# MCU.net
KiCad netlist of a schematic drawn in Altium Designer
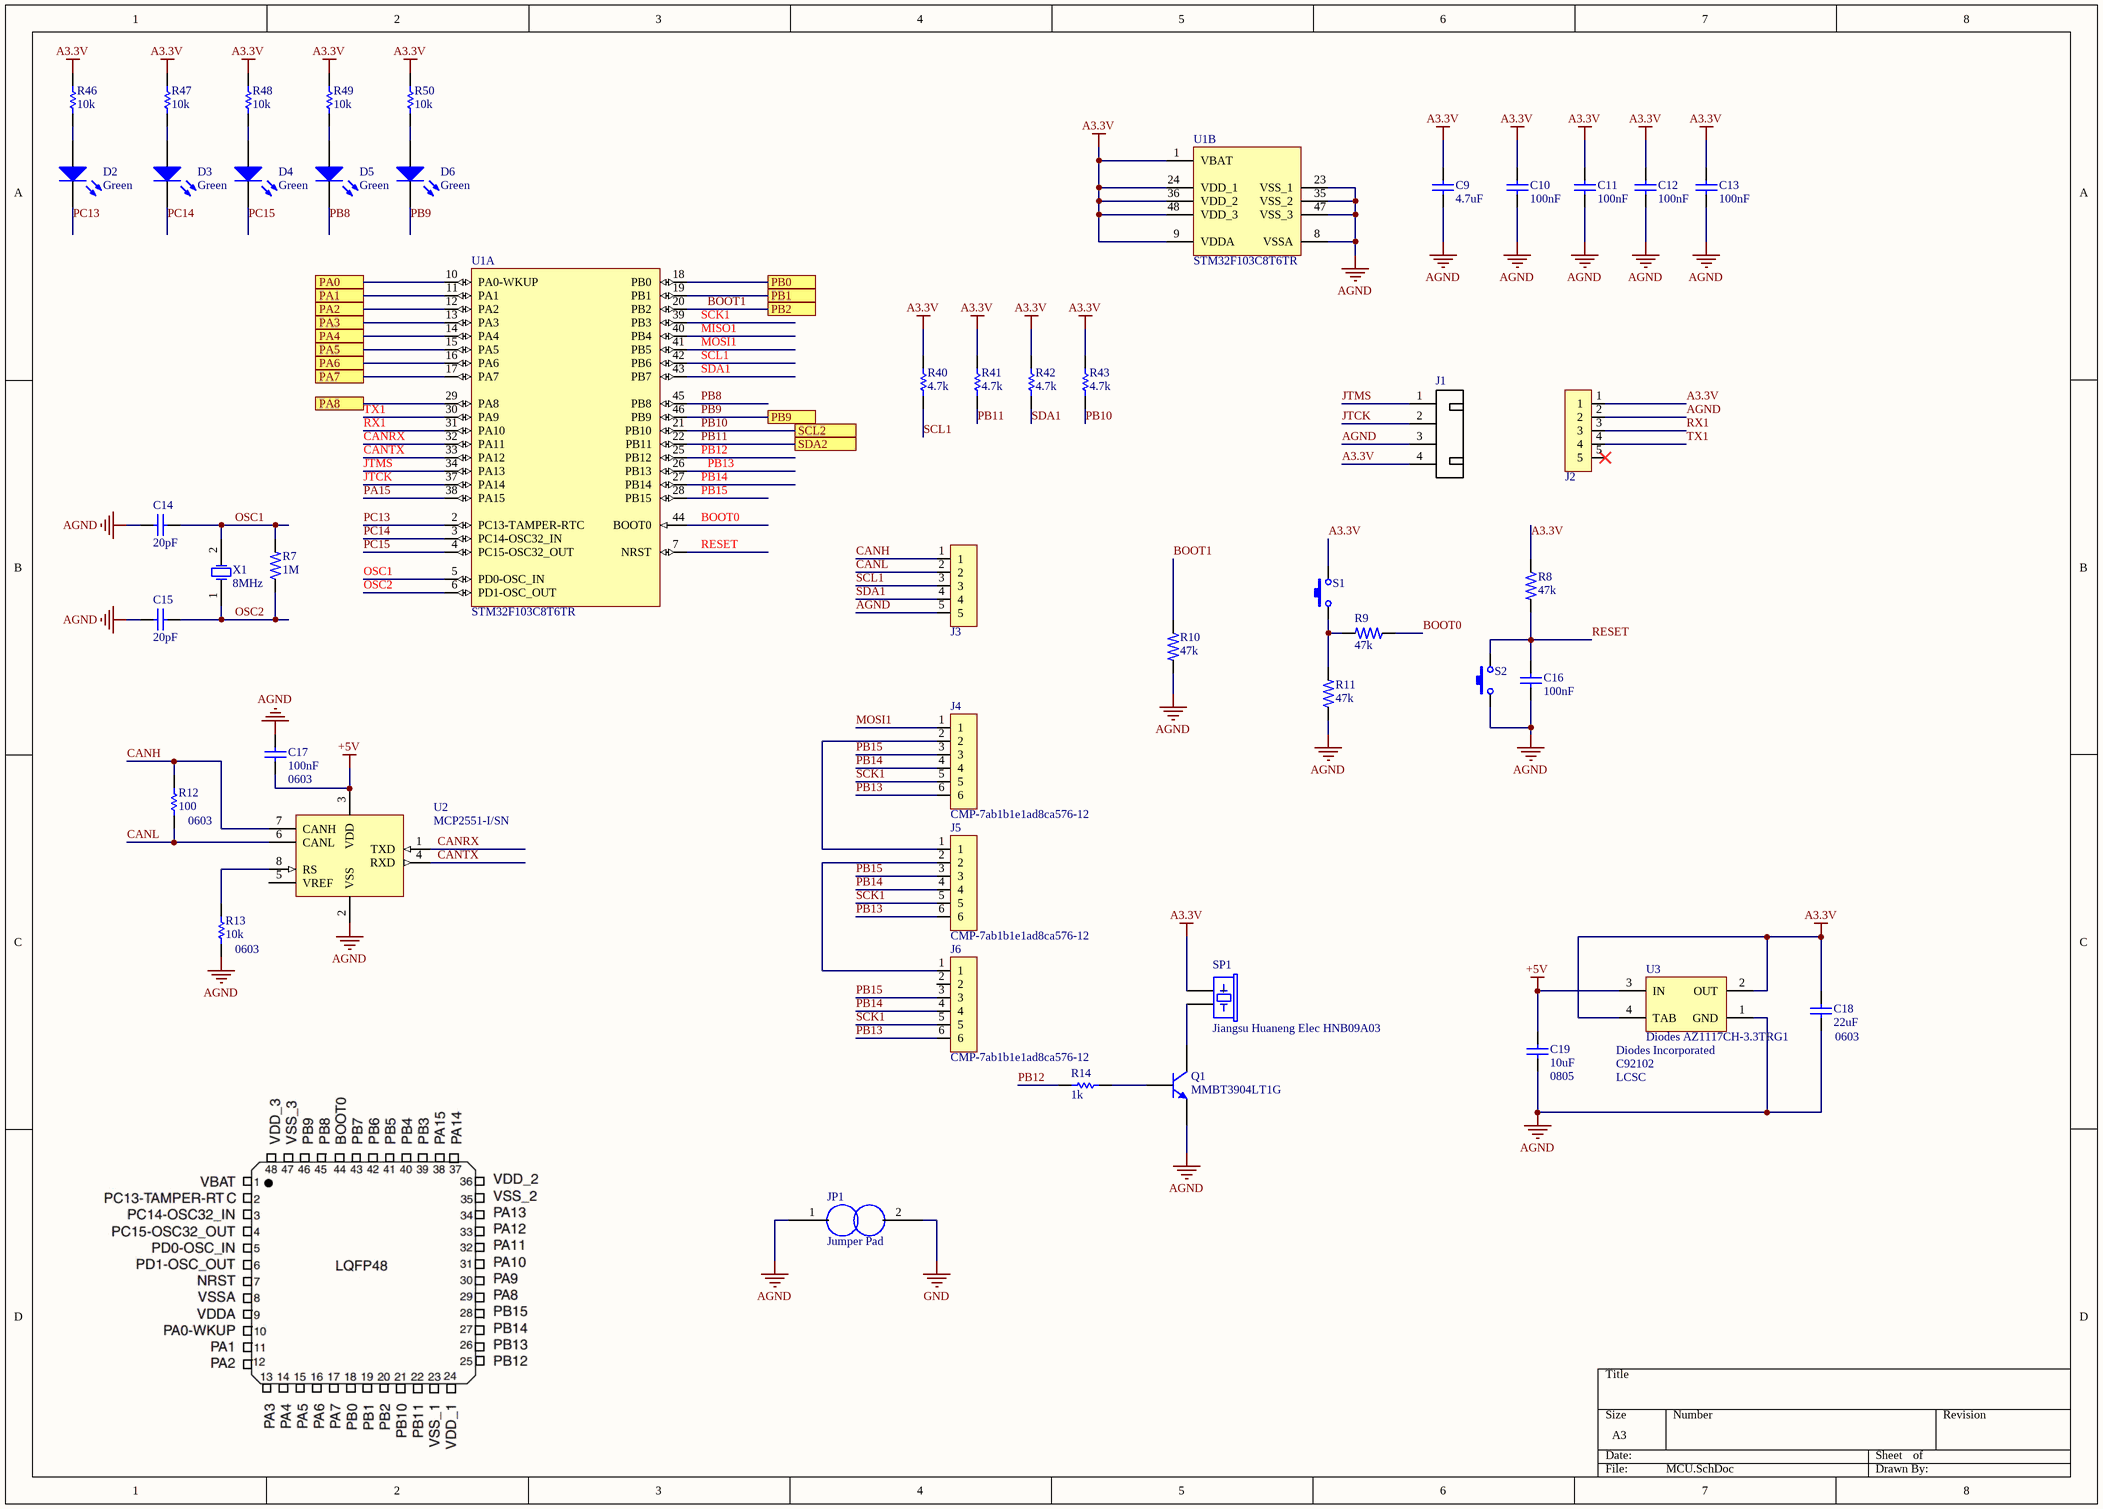
[diagram p0: MCU.SchDoc]

(export (version "E")
  (design (tool "Eeschema 10.0.6"))
  (components
    (comp (ref "C9")
      (value "4.7uF")
      (footprint "CAPC1608X09N")
      (description "0603 10 nF 50 V ± 10% Tolerance X7R Surface Mount Multilayer Ceramic Capacitor")
      (fields
        (field (name "MANUFACTURE PART NUMBER") "CL10A475KP8NNNC")
        (field (name "MANUFACTURER") "Samsung Electro-Mechanics")
      )
      (libsource (lib "POWER CARD") (part "CMP-2f55e5122ad9f092-5"))
    )
    (comp (ref "C10")
      (value "100nF")
      (footprint "CAPC1608X09N")
      (description "0603 10 nF 50 V ± 10% Tolerance X7R Surface Mount Multilayer Ceramic Capacitor")
      (fields
        (field (name "MANUFACTURE PART NUMBER") "CC0603KRX7R9BB104")
        (field (name "MANUFACTURER") "YAGEO")
      )
      (libsource (lib "POWER CARD") (part "CMP-2f55e5122ad9f092-5"))
    )
    (comp (ref "C11")
      (value "100nF")
      (footprint "CAPC1608X09N")
      (description "0603 10 nF 50 V ± 10% Tolerance X7R Surface Mount Multilayer Ceramic Capacitor")
      (fields
        (field (name "MANUFACTURE PART NUMBER") "CC0603KRX7R9BB104")
        (field (name "MANUFACTURER") "YAGEO")
      )
      (libsource (lib "POWER CARD") (part "CMP-2f55e5122ad9f092-5"))
    )
    (comp (ref "C12")
      (value "100nF")
      (footprint "CAPC1608X09N")
      (description "0603 10 nF 50 V ± 10% Tolerance X7R Surface Mount Multilayer Ceramic Capacitor")
      (fields
        (field (name "MANUFACTURE PART NUMBER") "CC0603KRX7R9BB104")
        (field (name "MANUFACTURER") "YAGEO")
      )
      (libsource (lib "POWER CARD") (part "CMP-2f55e5122ad9f092-5"))
    )
    (comp (ref "C13")
      (value "100nF")
      (footprint "CAPC1608X09N")
      (description "0603 10 nF 50 V ± 10% Tolerance X7R Surface Mount Multilayer Ceramic Capacitor")
      (fields
        (field (name "MANUFACTURE PART NUMBER") "CC0603KRX7R9BB104")
        (field (name "MANUFACTURER") "YAGEO")
      )
      (libsource (lib "POWER CARD") (part "CMP-2f55e5122ad9f092-5"))
    )
    (comp (ref "C14")
      (value "20pF")
      (footprint "CAPC1608X09N")
      (description "0603 10 nF 50 V ± 10% Tolerance X7R Surface Mount Multilayer Ceramic Capacitor")
      (fields
        (field (name "MANUFACTURE PART NUMBER") "CC0603JRNPO9BN200")
        (field (name "MANUFACTURER") "YAGEO")
      )
      (libsource (lib "POWER CARD") (part "CMP-2f55e5122ad9f092-5"))
    )
    (comp (ref "C15")
      (value "20pF")
      (footprint "CAPC1608X09N")
      (description "0603 10 nF 50 V ± 10% Tolerance X7R Surface Mount Multilayer Ceramic Capacitor")
      (fields
        (field (name "MANUFACTURE PART NUMBER") "CC0603JRNPO9BN200")
        (field (name "MANUFACTURER") "YAGEO")
      )
      (libsource (lib "POWER CARD") (part "CMP-2f55e5122ad9f092-5"))
    )
    (comp (ref "C16")
      (value "100nF")
      (footprint "CAPC1608X09N")
      (description "0603 10 nF 50 V ± 10% Tolerance X7R Surface Mount Multilayer Ceramic Capacitor")
      (fields
        (field (name "MANUFACTURE PART NUMBER") "CC0603KRX7R9BB104")
        (field (name "MANUFACTURER") "YAGEO")
      )
      (libsource (lib "POWER CARD") (part "CMP-2f55e5122ad9f092-5"))
    )
    (comp (ref "C17")
      (value "100nF")
      (footprint "CAPC1608X09N")
      (description "0603 10 nF 50 V ± 10% Tolerance X7R Surface Mount Multilayer Ceramic Capacitor")
      (fields
        (field (name "MANUFACTURE PART NUMBER") "CC0603KRX7R9BB104")
        (field (name "MANUFACTURER") "YAGEO")
        (field (name "PACKAGE / CASE") "0603")
      )
      (libsource (lib "POWER CARD") (part "CMP-2f55e5122ad9f092-5"))
    )
    (comp (ref "C18")
      (value "22uF")
      (footprint "CAPC1608X09N")
      (description "0603 10 nF 50 V ± 10% Tolerance X7R Surface Mount Multilayer Ceramic Capacitor")
      (fields
        (field (name "MANUFACTURE PART NUMBER") "CL10A226MP8NUNE")
        (field (name "MANUFACTURER") "Samsung Electro-Mechanics")
        (field (name "PACKAGE / CASE") "0603")
      )
      (libsource (lib "POWER CARD") (part "CMP-2f55e5122ad9f092-5"))
    )
    (comp (ref "C19")
      (value "10uF")
      (footprint "C0805")
      (description "Cap Ceramic 0.1uF 50V X7R 10% SMD 0805 125C Embossed T/R")
      (fields
        (field (name "MANUFACTURE PART NUMBER") "CL21B106KOQNNNE")
        (field (name "PACKAGE / CASE") "0805")
        (field (name "MANUFACTURER") "Samsung Electro-Mechanics")
      )
      (libsource (lib "POWER CARD") (part "CMP-135114-3"))
    )
    (comp (ref "D2")
      (value "Green")
      (footprint "PCBComponent_1 - duplicate")
      (description "Generic LED 0603")
      (fields (field (name "MANUFACTURER") "Orient") (field (name "MANUFACTURE PART NUMBER") "ORH-G36G"))
      (libsource (lib "POWER CARD") (part "CMP-7ejgl1mi36gtz3spabtw-1"))
    )
    (comp (ref "D3")
      (value "Green")
      (footprint "PCBComponent_1 - duplicate")
      (description "Generic LED 0603")
      (fields (field (name "MANUFACTURER") "Orient") (field (name "MANUFACTURE PART NUMBER") "ORH-G36G"))
      (libsource (lib "POWER CARD") (part "CMP-7ejgl1mi36gtz3spabtw-1"))
    )
    (comp (ref "D4")
      (value "Green")
      (footprint "PCBComponent_1 - duplicate")
      (description "Generic LED 0603")
      (fields (field (name "MANUFACTURER") "Orient") (field (name "MANUFACTURE PART NUMBER") "ORH-G36G"))
      (libsource (lib "POWER CARD") (part "CMP-7ejgl1mi36gtz3spabtw-1"))
    )
    (comp (ref "D5")
      (value "Green")
      (footprint "PCBComponent_1 - duplicate")
      (description "Generic LED 0603")
      (fields (field (name "MANUFACTURER") "Orient") (field (name "MANUFACTURE PART NUMBER") "ORH-G36G"))
      (libsource (lib "POWER CARD") (part "CMP-7ejgl1mi36gtz3spabtw-1"))
    )
    (comp (ref "D6")
      (value "Green")
      (footprint "PCBComponent_1 - duplicate")
      (description "Generic LED 0603")
      (fields (field (name "MANUFACTURER") "Orient") (field (name "MANUFACTURE PART NUMBER") "ORH-G36G"))
      (libsource (lib "POWER CARD") (part "CMP-7ejgl1mi36gtz3spabtw-1"))
    )
    (comp (ref "J1")
      (value "CMP-a6466f3bff057981-11")
      (footprint "PCB-z52whxwf67d3eu6gna8s-1")
      (description "XH Series 4 Position 2.5 mm Pitch Through Hole Crimp Top Entry Shrouded Header")
      (fields
        (field (name "MANUFACTURE PART NUMBER") "B4B-XH-A (LF)(SN)")
        (field (name "MANUFACTURER") "JST Sales America")
      )
      (libsource (lib "POWER CARD") (part "CMP-a6466f3bff057981-11"))
    )
    (comp (ref "J2")
      (value "TE Connectivity / AMP 3-644456-5")
      (footprint "PCB-rnlen50cc5tt6vc22c1r-1")
      (description "MTA-100 5 Position Through-Hole Single Row Straight Wire to Board Header")
      (libsource (lib "POWER CARD") (part "CMP-b5d67e8662e76a11-19"))
    )
    (comp (ref "J3")
      (value "TE Connectivity / AMP 3-644456-5")
      (footprint "PCB-rnlen50cc5tt6vc22c1r-1")
      (description "MTA-100 5 Position Through-Hole Single Row Straight Wire to Board Header")
      (libsource (lib "") (part "CMP-b5d67e8662e76a11-19_1"))
    )
    (comp (ref "J4")
      (value "CMP-7ab1b1e1ad8ca576-12")
      (footprint "PCB-oudem42uhcimrbfznktg-1")
      (description "MTA-100 Series 6 Position 2.54 mm Pitch Single Row Tin Plated Header")
      (libsource (lib "POWER CARD") (part "CMP-7ab1b1e1ad8ca576-12"))
    )
    (comp (ref "J5")
      (value "CMP-7ab1b1e1ad8ca576-12")
      (footprint "PCB-oudem42uhcimrbfznktg-1")
      (description "MTA-100 Series 6 Position 2.54 mm Pitch Single Row Tin Plated Header")
      (libsource (lib "POWER CARD") (part "CMP-7ab1b1e1ad8ca576-12"))
    )
    (comp (ref "J6")
      (value "CMP-7ab1b1e1ad8ca576-12")
      (footprint "PCB-oudem42uhcimrbfznktg-1")
      (description "MTA-100 Series 6 Position 2.54 mm Pitch Single Row Tin Plated Header")
      (libsource (lib "POWER CARD") (part "CMP-7ab1b1e1ad8ca576-12"))
    )
    (comp (ref "JP1")
      (value "Jumper Pad")
      (footprint "PCB-sjva3kmaxrqfkswkvsp7-1")
      (description "JP")
      (libsource (lib "POWER CARD") (part "CMP-75tq5o8j4p0avfd6ylbk-1"))
    )
    (comp (ref "Q1")
      (value "MMBT3904LT1G")
      (footprint "SOT-23")
      (description "MMBT Series 40 V 200 mA SMT NPN Silicon General Purpose Transistor - SOT-23")
      (fields (field (name "MANUFACTURER") "ON Semiconductor"))
      (libsource (lib "POWER CARD") (part "CMP-857799-8"))
    )
    (comp (ref "R7")
      (value "1M")
      (footprint "PCB-3elf45qdqizoabmczrxc-1")
      (description "Surface Mount Thick Film Resistor, RC Series, 1 kohm, 100 mW, - 1%, 50 V, 0603 [1608 Metric]")
      (fields
        (field (name "MANUFACTURER") "UNI-ROYAL(Uniroyal Elec)")
        (field (name "MANUFACTURE PART NUMBER") "0603WAF1004T5E")
      )
      (libsource (lib "POWER CARD") (part "CMP-1853278-23"))
    )
    (comp (ref "R8")
      (value "47k")
      (footprint "PCB-3elf45qdqizoabmczrxc-1")
      (description "Surface Mount Thick Film Resistor, RC Series, 1 kohm, 100 mW, - 1%, 50 V, 0603 [1608 Metric]")
      (fields
        (field (name "MANUFACTURER") "UNI-ROYAL(Uniroyal Elec)")
        (field (name "MANUFACTURE PART NUMBER") "0603WAF4702T5E")
      )
      (libsource (lib "POWER CARD") (part "CMP-1853278-23"))
    )
    (comp (ref "R9")
      (value "47k")
      (footprint "PCB-3elf45qdqizoabmczrxc-1")
      (description "Surface Mount Thick Film Resistor, RC Series, 1 kohm, 100 mW, - 1%, 50 V, 0603 [1608 Metric]")
      (fields
        (field (name "MANUFACTURER") "UNI-ROYAL(Uniroyal Elec)")
        (field (name "MANUFACTURE PART NUMBER") "0603WAF4702T5E")
      )
      (libsource (lib "POWER CARD") (part "CMP-1853278-23"))
    )
    (comp (ref "R10")
      (value "47k")
      (footprint "PCB-3elf45qdqizoabmczrxc-1")
      (description "Surface Mount Thick Film Resistor, RC Series, 1 kohm, 100 mW, - 1%, 50 V, 0603 [1608 Metric]")
      (fields
        (field (name "MANUFACTURER") "UNI-ROYAL(Uniroyal Elec)")
        (field (name "MANUFACTURE PART NUMBER") "0603WAF4702T5E")
      )
      (libsource (lib "POWER CARD") (part "CMP-1853278-23"))
    )
    (comp (ref "R11")
      (value "47k")
      (footprint "PCB-3elf45qdqizoabmczrxc-1")
      (description "Surface Mount Thick Film Resistor, RC Series, 1 kohm, 100 mW, - 1%, 50 V, 0603 [1608 Metric]")
      (fields
        (field (name "MANUFACTURER") "UNI-ROYAL(Uniroyal Elec)")
        (field (name "MANUFACTURE PART NUMBER") "0603WAF4702T5E")
      )
      (libsource (lib "POWER CARD") (part "CMP-1853278-23"))
    )
    (comp (ref "R12")
      (value "100")
      (footprint "gen0603-2")
      (description "Surface Mount Thick Film Resistor, RC Series, 1 kohm, 100 mW, - 1%, 50 V, 0603 [1608 Metric]")
      (fields
        (field (name "MANUFACTURER") "UNI-ROYAL(Uniroyal Elec)")
        (field (name "MANUFACTURE PART NUMBER") "0603WAF1000T5E")
        (field (name "PACKAGE / CASE") "0603")
      )
      (libsource (lib "POWER CARD") (part "CMP-1853278-27"))
    )
    (comp (ref "R13")
      (value "10k")
      (footprint "gen0603-2")
      (description "Surface Mount Thick Film Resistor, RC Series, 1 kohm, 100 mW, - 1%, 50 V, 0603 [1608 Metric]")
      (fields
        (field (name "MANUFACTURER") "YAGEO")
        (field (name "MANUFACTURE PART NUMBER") "RC0603FR-0710KL")
        (field (name "PACKAGE / CASE") "0603")
      )
      (libsource (lib "POWER CARD") (part "CMP-1853278-27"))
    )
    (comp (ref "R14")
      (value "1k")
      (footprint "gen0603-2")
      (description "Surface Mount Thick Film Resistor, RC Series, 1 kohm, 100 mW, - 1%, 50 V, 0603 [1608 Metric]")
      (fields (field (name "MANUFACTURER") "YAGEO") (field (name "MANUFACTURE PART NUMBER") "RC0603FR-071KL"))
      (libsource (lib "Resistor Capacitor") (part "CMP-1853278-27_16"))
    )
    (comp (ref "R40")
      (value "4.7k")
      (footprint "gen0603-2")
      (description "Surface Mount Thick Film Resistor, RC Series, 1 kohm, 100 mW, - 1%, 50 V, 0603 [1608 Metric]")
      (fields
        (field (name "MANUFACTURE PART NUMBER") "RC0603FR-074K7L")
        (field (name "MANUFACTURER") "YAGEO")
      )
      (libsource (lib "POWER CARD") (part "CMP-1853278-27"))
    )
    (comp (ref "R41")
      (value "4.7k")
      (footprint "gen0603-2")
      (description "Surface Mount Thick Film Resistor, RC Series, 1 kohm, 100 mW, - 1%, 50 V, 0603 [1608 Metric]")
      (fields
        (field (name "MANUFACTURE PART NUMBER") "RC0603FR-074K7L")
        (field (name "MANUFACTURER") "YAGEO")
      )
      (libsource (lib "POWER CARD") (part "CMP-1853278-27"))
    )
    (comp (ref "R42")
      (value "4.7k")
      (footprint "gen0603-2")
      (description "Surface Mount Thick Film Resistor, RC Series, 1 kohm, 100 mW, - 1%, 50 V, 0603 [1608 Metric]")
      (fields
        (field (name "MANUFACTURE PART NUMBER") "RC0603FR-074K7L")
        (field (name "MANUFACTURER") "YAGEO")
      )
      (libsource (lib "POWER CARD") (part "CMP-1853278-27"))
    )
    (comp (ref "R43")
      (value "4.7k")
      (footprint "gen0603-2")
      (description "Surface Mount Thick Film Resistor, RC Series, 1 kohm, 100 mW, - 1%, 50 V, 0603 [1608 Metric]")
      (fields
        (field (name "MANUFACTURE PART NUMBER") "RC0603FR-074K7L")
        (field (name "MANUFACTURER") "YAGEO")
      )
      (libsource (lib "POWER CARD") (part "CMP-1853278-27"))
    )
    (comp (ref "R46")
      (value "10k")
      (footprint "gen0603-2")
      (description "Surface Mount Thick Film Resistor, RC Series, 1 kohm, 100 mW, - 1%, 50 V, 0603 [1608 Metric]")
      (fields
        (field (name "MANUFACTURER") "YAGEO")
        (field (name "MANUFACTURE PART NUMBER") "RC0603FR-0710KL")
      )
      (libsource (lib "POWER CARD") (part "CMP-1853278-27"))
    )
    (comp (ref "R47")
      (value "10k")
      (footprint "gen0603-2")
      (description "Surface Mount Thick Film Resistor, RC Series, 1 kohm, 100 mW, - 1%, 50 V, 0603 [1608 Metric]")
      (fields
        (field (name "MANUFACTURER") "YAGEO")
        (field (name "MANUFACTURE PART NUMBER") "RC0603FR-0710KL")
      )
      (libsource (lib "POWER CARD") (part "CMP-1853278-27"))
    )
    (comp (ref "R48")
      (value "10k")
      (footprint "gen0603-2")
      (description "Surface Mount Thick Film Resistor, RC Series, 1 kohm, 100 mW, - 1%, 50 V, 0603 [1608 Metric]")
      (fields
        (field (name "MANUFACTURER") "YAGEO")
        (field (name "MANUFACTURE PART NUMBER") "RC0603FR-0710KL")
      )
      (libsource (lib "POWER CARD") (part "CMP-1853278-27"))
    )
    (comp (ref "R49")
      (value "10k")
      (footprint "gen0603-2")
      (description "Surface Mount Thick Film Resistor, RC Series, 1 kohm, 100 mW, - 1%, 50 V, 0603 [1608 Metric]")
      (fields
        (field (name "MANUFACTURER") "YAGEO")
        (field (name "MANUFACTURE PART NUMBER") "RC0603FR-0710KL")
      )
      (libsource (lib "POWER CARD") (part "CMP-1853278-27"))
    )
    (comp (ref "R50")
      (value "10k")
      (footprint "gen0603-2")
      (description "Surface Mount Thick Film Resistor, RC Series, 1 kohm, 100 mW, - 1%, 50 V, 0603 [1608 Metric]")
      (fields
        (field (name "MANUFACTURER") "YAGEO")
        (field (name "MANUFACTURE PART NUMBER") "RC0603FR-0710KL")
      )
      (libsource (lib "POWER CARD") (part "CMP-1853278-27"))
    )
    (comp (ref "S1")
      (value "CMP-3c1bf499dccde3dc-3")
      (footprint "PCB-884bonwl6v4pb9lbnr4u-1")
      (description "Switch Tactile N.O. SPST Rectangular Button Gull Wing 0.05A 12VDC 2.45N SMD")
      (fields
        (field (name "MANUFACTURE PART NUMBER") "K2-1107ST-A4SW-06")
        (field (name "MANUFACTURER") "Korean Hroparts Elec")
      )
      (libsource (lib "POWER CARD") (part "CMP-3c1bf499dccde3dc-3"))
    )
    (comp (ref "S2")
      (value "CMP-3c1bf499dccde3dc-3")
      (footprint "PCB-884bonwl6v4pb9lbnr4u-1")
      (description "Switch Tactile N.O. SPST Rectangular Button Gull Wing 0.05A 12VDC 2.45N SMD")
      (fields
        (field (name "MANUFACTURE PART NUMBER") "K2-1107ST-A4SW-06")
        (field (name "MANUFACTURER") "Korean Hroparts Elec")
      )
      (libsource (lib "POWER CARD") (part "CMP-3c1bf499dccde3dc-3"))
    )
    (comp (ref "SP1")
      (value "Jiangsu Huaneng Elec HNB09A03")
      (footprint "PCB-gql0f0yk39bxcwo1gexj-1")
      (description "Magnetic YES 3000±300Hz 90dB @ 3V, 10cm 3V ?9mm 9*5.5mm Buzzers RoHS")
      (fields
        (field (name "MANUFACTURER") "Jiangsu Huaneng Elec")
        (field (name "MANUFACTURE PART NUMBER") "HNB09A03")
      )
      (libsource (lib "POWER CARD") (part "CMP-8r7wb9d4hsrx0vdasxxy-1"))
    )
    (comp (ref "U1")
      (value "STM32F103C8T6TR")
      (footprint "STM-LQFP48_M")
      (fields
        (field (name "MANUFACTURE PART NUMBER") "STM32F103C8T6")
        (field (name "MANUFACTURER") "STMicroelectronics")
      )
      (libsource (lib "POWER CARD") (part "CMP-2954476-4"))
    )
    (comp (ref "U2")
      (value "MCP2551-I/SN")
      (footprint "PCB-j27wim3vo61mdxz6aows-1")
      (description "Microchip MCP2551-I/SN; CAN Transceiver1Mbit/s 1-channel ISO 11898; 8-Pin SOIC")
      (fields (field (name "MANUFACTURER") "Microchip Tech"))
      (libsource (lib "POWER CARD") (part "MCP2551-I/SN"))
    )
    (comp (ref "U3")
      (value "Diodes AZ1117CH-3.3TRG1")
      (footprint "PCB-15095235-1")
      (description "IC REG LDO 3.3V 0.8A SOT223")
      (fields
        (field (name "MANUFACTURE PART NUMBER") "AZ1117CH-3.3TRG1")
        (field (name "MANUFACTURER") "Diodes Incorporated")
        (field (name "SUPPLIER PART NUMBER") "C92102")
        (field (name "SUPPLIER") "LCSC")
      )
      (libsource (lib "POWER CARD") (part "CMP-15095235-4"))
    )
    (comp (ref "X1")
      (value "8MHz")
      (footprint "XTAL1")
      (description "Microprocessor, Crystal; 8 MHz; 30 ppm (Typ.) @ degC; 7 pF (Max.); 20 pF")
      (fields
        (field (name "MANUFACTURER") "Yangxing Tech")
        (field (name "MANUFACTURE PART NUMBER") "X49SD8MSD2SC")
      )
      (libsource (lib "POWER CARD") (part "CMP-4bca809c9193940d-1"))
    )
  )
  (nets
    (net (code "1") (name "+5V") (class "Default")
      (node (ref "C17") (pin "2") (pinfunction "2_2") (pintype "passive"))
      (node (ref "C19") (pin "2") (pinfunction "2_2") (pintype "passive"))
      (node (ref "U2") (pin "3") (pinfunction "VDD_3") (pintype "power_in"))
      (node (ref "U3") (pin "3") (pinfunction "IN_3") (pintype "power_in"))
    )
    (net (code "2") (name "/BOOT0") (class "Default")
      (node (ref "R9") (pin "1") (pinfunction "1_1") (pintype "passive"))
      (node (ref "U1") (pin "44") (pinfunction "BOOT0_44") (pintype "input"))
    )
    (net (code "3") (name "/BOOT1") (class "Default")
      (node (ref "R10") (pin "1") (pinfunction "1_1") (pintype "passive"))
      (node (ref "U1") (pin "20") (pinfunction "PB2_20") (pintype "bidirectional"))
    )
    (net (code "4") (name "/CANH") (class "Default")
      (node (ref "J3") (pin "1") (pinfunction "1_1") (pintype "passive"))
      (node (ref "R12") (pin "2") (pinfunction "2_2") (pintype "passive"))
      (node (ref "U2") (pin "7") (pinfunction "CANH_7") (pintype "passive"))
    )
    (net (code "5") (name "/CANL") (class "Default")
      (node (ref "J3") (pin "2") (pinfunction "2_2") (pintype "passive"))
      (node (ref "R12") (pin "1") (pinfunction "1_1") (pintype "passive"))
      (node (ref "U2") (pin "6") (pinfunction "CANL_6") (pintype "passive"))
    )
    (net (code "6") (name "/CANRX") (class "Default")
      (node (ref "U1") (pin "32") (pinfunction "PA11_32") (pintype "bidirectional"))
      (node (ref "U2") (pin "1") (pinfunction "TXD_1") (pintype "input"))
    )
    (net (code "7") (name "/CANTX") (class "Default")
      (node (ref "U1") (pin "33") (pinfunction "PA12_33") (pintype "bidirectional"))
      (node (ref "U2") (pin "4") (pinfunction "RXD_4") (pintype "output"))
    )
    (net (code "8") (name "/JTCK") (class "Default")
      (node (ref "J1") (pin "2") (pinfunction "2_2") (pintype "passive"))
      (node (ref "U1") (pin "37") (pinfunction "PA14_37") (pintype "bidirectional"))
    )
    (net (code "9") (name "/JTMS") (class "Default")
      (node (ref "J1") (pin "1") (pinfunction "1_1") (pintype "passive"))
      (node (ref "U1") (pin "34") (pinfunction "PA13_34") (pintype "bidirectional"))
    )
    (net (code "10") (name "/MISO1") (class "Default")
      (node (ref "U1") (pin "40") (pinfunction "PB4_40") (pintype "bidirectional"))
    )
    (net (code "11") (name "/MOSI1") (class "Default")
      (node (ref "J4") (pin "1") (pinfunction "1_1") (pintype "passive"))
      (node (ref "U1") (pin "41") (pinfunction "PB5_41") (pintype "bidirectional"))
    )
    (net (code "12") (name "/OSC1") (class "Default")
      (node (ref "C14") (pin "1") (pinfunction "1_1") (pintype "passive"))
      (node (ref "R7") (pin "2") (pinfunction "2_2") (pintype "passive"))
      (node (ref "U1") (pin "5") (pinfunction "PD0-OSC_IN_5") (pintype "bidirectional"))
      (node (ref "X1") (pin "2") (pinfunction "X2_2") (pintype "passive"))
    )
    (net (code "13") (name "/OSC2") (class "Default")
      (node (ref "C15") (pin "1") (pinfunction "1_1") (pintype "passive"))
      (node (ref "R7") (pin "1") (pinfunction "1_1") (pintype "passive"))
      (node (ref "U1") (pin "6") (pinfunction "PD1-OSC_OUT_6") (pintype "bidirectional"))
      (node (ref "X1") (pin "1") (pinfunction "X1_1") (pintype "passive"))
    )
    (net (code "14") (name "/PA0") (class "Default")
      (node (ref "U1") (pin "10") (pinfunction "PA0-WKUP_10") (pintype "bidirectional"))
    )
    (net (code "15") (name "/PA1") (class "Default")
      (node (ref "U1") (pin "11") (pinfunction "PA1_11") (pintype "bidirectional"))
    )
    (net (code "16") (name "/PA2") (class "Default")
      (node (ref "U1") (pin "12") (pinfunction "PA2_12") (pintype "bidirectional"))
    )
    (net (code "17") (name "/PA3") (class "Default")
      (node (ref "U1") (pin "13") (pinfunction "PA3_13") (pintype "bidirectional"))
    )
    (net (code "18") (name "/PA4") (class "Default")
      (node (ref "U1") (pin "14") (pinfunction "PA4_14") (pintype "bidirectional"))
    )
    (net (code "19") (name "/PA5") (class "Default")
      (node (ref "U1") (pin "15") (pinfunction "PA5_15") (pintype "bidirectional"))
    )
    (net (code "20") (name "/PA6") (class "Default")
      (node (ref "U1") (pin "16") (pinfunction "PA6_16") (pintype "bidirectional"))
    )
    (net (code "21") (name "/PA7") (class "Default")
      (node (ref "U1") (pin "17") (pinfunction "PA7_17") (pintype "bidirectional"))
    )
    (net (code "22") (name "/PA8") (class "Default")
      (node (ref "U1") (pin "29") (pinfunction "PA8_29") (pintype "bidirectional"))
    )
    (net (code "23") (name "/PA15") (class "Default")
      (node (ref "U1") (pin "38") (pinfunction "PA15_38") (pintype "bidirectional"))
    )
    (net (code "24") (name "/PB0") (class "Default")
      (node (ref "U1") (pin "18") (pinfunction "PB0_18") (pintype "bidirectional"))
    )
    (net (code "25") (name "/PB1") (class "Default")
      (node (ref "U1") (pin "19") (pinfunction "PB1_19") (pintype "bidirectional"))
    )
    (net (code "26") (name "/PB8") (class "Default")
      (node (ref "D5") (pin "2") (pinfunction "K_2") (pintype "passive"))
      (node (ref "U1") (pin "45") (pinfunction "PB8_45") (pintype "bidirectional"))
    )
    (net (code "27") (name "/PB9") (class "Default")
      (node (ref "D6") (pin "2") (pinfunction "K_2") (pintype "passive"))
      (node (ref "U1") (pin "46") (pinfunction "PB9_46") (pintype "bidirectional"))
    )
    (net (code "28") (name "/PB10") (class "Default")
      (node (ref "R43") (pin "1") (pinfunction "1_1") (pintype "passive"))
      (node (ref "U1") (pin "21") (pinfunction "PB10_21") (pintype "bidirectional"))
    )
    (net (code "29") (name "/PB11") (class "Default")
      (node (ref "R41") (pin "1") (pinfunction "1_1") (pintype "passive"))
      (node (ref "U1") (pin "22") (pinfunction "PB11_22") (pintype "bidirectional"))
    )
    (net (code "30") (name "/PB12") (class "Default")
      (node (ref "R14") (pin "2") (pinfunction "2_2") (pintype "passive"))
      (node (ref "U1") (pin "25") (pinfunction "PB12_25") (pintype "bidirectional"))
    )
    (net (code "31") (name "/PB13") (class "Default")
      (node (ref "J4") (pin "6") (pinfunction "6_6") (pintype "passive"))
      (node (ref "J5") (pin "6") (pinfunction "6_6") (pintype "passive"))
      (node (ref "J6") (pin "6") (pinfunction "6_6") (pintype "passive"))
      (node (ref "U1") (pin "26") (pinfunction "PB13_26") (pintype "bidirectional"))
    )
    (net (code "32") (name "/PB14") (class "Default")
      (node (ref "J4") (pin "4") (pinfunction "4_4") (pintype "passive"))
      (node (ref "J5") (pin "4") (pinfunction "4_4") (pintype "passive"))
      (node (ref "J6") (pin "4") (pinfunction "4_4") (pintype "passive"))
      (node (ref "U1") (pin "27") (pinfunction "PB14_27") (pintype "bidirectional"))
    )
    (net (code "33") (name "/PB15") (class "Default")
      (node (ref "J4") (pin "3") (pinfunction "3_3") (pintype "passive"))
      (node (ref "J5") (pin "3") (pinfunction "3_3") (pintype "passive"))
      (node (ref "J6") (pin "3") (pinfunction "3_3") (pintype "passive"))
      (node (ref "U1") (pin "28") (pinfunction "PB15_28") (pintype "bidirectional"))
    )
    (net (code "34") (name "/PC13") (class "Default")
      (node (ref "D2") (pin "2") (pinfunction "K_2") (pintype "passive"))
      (node (ref "U1") (pin "2") (pinfunction "PC13-TAMPER-RTC_2") (pintype "bidirectional"))
    )
    (net (code "35") (name "/PC14") (class "Default")
      (node (ref "D3") (pin "2") (pinfunction "K_2") (pintype "passive"))
      (node (ref "U1") (pin "3") (pinfunction "PC14-OSC32_IN_3") (pintype "bidirectional"))
    )
    (net (code "36") (name "/PC15") (class "Default")
      (node (ref "D4") (pin "2") (pinfunction "K_2") (pintype "passive"))
      (node (ref "U1") (pin "4") (pinfunction "PC15-OSC32_OUT_4") (pintype "bidirectional"))
    )
    (net (code "37") (name "/RESET") (class "Default")
      (node (ref "C16") (pin "2") (pinfunction "2_2") (pintype "passive"))
      (node (ref "R8") (pin "2") (pinfunction "2_2") (pintype "passive"))
      (node (ref "S2") (pin "2") (pinfunction "2_2") (pintype "passive"))
      (node (ref "U1") (pin "7") (pinfunction "NRST_7") (pintype "bidirectional"))
    )
    (net (code "38") (name "/RX1") (class "Default")
      (node (ref "J2") (pin "3") (pinfunction "3_3") (pintype "passive"))
      (node (ref "U1") (pin "31") (pinfunction "PA10_31") (pintype "bidirectional"))
    )
    (net (code "39") (name "/SCK1") (class "Default")
      (node (ref "J4") (pin "5") (pinfunction "5_5") (pintype "passive"))
      (node (ref "J5") (pin "5") (pinfunction "5_5") (pintype "passive"))
      (node (ref "J6") (pin "5") (pinfunction "5_5") (pintype "passive"))
      (node (ref "U1") (pin "39") (pinfunction "PB3_39") (pintype "bidirectional"))
    )
    (net (code "40") (name "/SCL1") (class "Default")
      (node (ref "J3") (pin "3") (pinfunction "3_3") (pintype "passive"))
      (node (ref "R40") (pin "1") (pinfunction "1_1") (pintype "passive"))
      (node (ref "U1") (pin "42") (pinfunction "PB6_42") (pintype "bidirectional"))
    )
    (net (code "41") (name "/SDA1") (class "Default")
      (node (ref "J3") (pin "4") (pinfunction "4_4") (pintype "passive"))
      (node (ref "R42") (pin "1") (pinfunction "1_1") (pintype "passive"))
      (node (ref "U1") (pin "43") (pinfunction "PB7_43") (pintype "bidirectional"))
    )
    (net (code "42") (name "/TX1") (class "Default")
      (node (ref "J2") (pin "4") (pinfunction "4_4") (pintype "passive"))
      (node (ref "U1") (pin "30") (pinfunction "PA9_30") (pintype "bidirectional"))
    )
    (net (code "43") (name "A3.3V") (class "Default")
      (node (ref "C10") (pin "2") (pinfunction "2_2") (pintype "passive"))
      (node (ref "C11") (pin "2") (pinfunction "2_2") (pintype "passive"))
      (node (ref "C12") (pin "2") (pinfunction "2_2") (pintype "passive"))
      (node (ref "C13") (pin "2") (pinfunction "2_2") (pintype "passive"))
      (node (ref "C18") (pin "2") (pinfunction "2_2") (pintype "passive"))
      (node (ref "C9") (pin "2") (pinfunction "2_2") (pintype "passive"))
      (node (ref "J1") (pin "4") (pinfunction "4_4") (pintype "passive"))
      (node (ref "J2") (pin "1") (pinfunction "1_1") (pintype "passive"))
      (node (ref "R40") (pin "2") (pinfunction "2_2") (pintype "passive"))
      (node (ref "R41") (pin "2") (pinfunction "2_2") (pintype "passive"))
      (node (ref "R42") (pin "2") (pinfunction "2_2") (pintype "passive"))
      (node (ref "R43") (pin "2") (pinfunction "2_2") (pintype "passive"))
      (node (ref "R46") (pin "2") (pinfunction "2_2") (pintype "passive"))
      (node (ref "R47") (pin "2") (pinfunction "2_2") (pintype "passive"))
      (node (ref "R48") (pin "2") (pinfunction "2_2") (pintype "passive"))
      (node (ref "R49") (pin "2") (pinfunction "2_2") (pintype "passive"))
      (node (ref "R50") (pin "2") (pinfunction "2_2") (pintype "passive"))
      (node (ref "R8") (pin "1") (pinfunction "1_1") (pintype "passive"))
      (node (ref "S1") (pin "2") (pinfunction "2_2") (pintype "passive"))
      (node (ref "SP1") (pin "1") (pinfunction "+_1") (pintype "passive"))
      (node (ref "U1") (pin "1") (pinfunction "VBAT_1") (pintype "power_in"))
      (node (ref "U1") (pin "24") (pinfunction "VDD_1_24") (pintype "power_in"))
      (node (ref "U1") (pin "36") (pinfunction "VDD_2_36") (pintype "power_in"))
      (node (ref "U1") (pin "48") (pinfunction "VDD_3_48") (pintype "power_in"))
      (node (ref "U1") (pin "9") (pinfunction "VDDA_9") (pintype "power_in"))
      (node (ref "U3") (pin "2") (pinfunction "OUT_2") (pintype "power_in"))
      (node (ref "U3") (pin "4") (pinfunction "TAB_4") (pintype "power_in"))
    )
    (net (code "44") (name "AGND") (class "Default")
      (node (ref "C10") (pin "1") (pinfunction "1_1") (pintype "passive"))
      (node (ref "C11") (pin "1") (pinfunction "1_1") (pintype "passive"))
      (node (ref "C12") (pin "1") (pinfunction "1_1") (pintype "passive"))
      (node (ref "C13") (pin "1") (pinfunction "1_1") (pintype "passive"))
      (node (ref "C14") (pin "2") (pinfunction "2_2") (pintype "passive"))
      (node (ref "C15") (pin "2") (pinfunction "2_2") (pintype "passive"))
      (node (ref "C16") (pin "1") (pinfunction "1_1") (pintype "passive"))
      (node (ref "C17") (pin "1") (pinfunction "1_1") (pintype "passive"))
      (node (ref "C18") (pin "1") (pinfunction "1_1") (pintype "passive"))
      (node (ref "C19") (pin "1") (pinfunction "1_1") (pintype "passive"))
      (node (ref "C9") (pin "1") (pinfunction "1_1") (pintype "passive"))
      (node (ref "J1") (pin "3") (pinfunction "3_3") (pintype "passive"))
      (node (ref "J2") (pin "2") (pinfunction "2_2") (pintype "passive"))
      (node (ref "J3") (pin "5") (pinfunction "5_5") (pintype "passive"))
      (node (ref "JP1") (pin "1") (pintype "passive"))
      (node (ref "Q1") (pin "2") (pinfunction "E_2") (pintype "passive"))
      (node (ref "R10") (pin "2") (pinfunction "2_2") (pintype "passive"))
      (node (ref "R11") (pin "1") (pinfunction "1_1") (pintype "passive"))
      (node (ref "R13") (pin "1") (pinfunction "1_1") (pintype "passive"))
      (node (ref "S2") (pin "1") (pinfunction "1_1") (pintype "passive"))
      (node (ref "U1") (pin "23") (pinfunction "VSS_1_23") (pintype "power_in"))
      (node (ref "U1") (pin "35") (pinfunction "VSS_2_35") (pintype "power_in"))
      (node (ref "U1") (pin "47") (pinfunction "VSS_3_47") (pintype "power_in"))
      (node (ref "U1") (pin "8") (pinfunction "VSSA_8") (pintype "power_in"))
      (node (ref "U2") (pin "2") (pinfunction "VSS_2") (pintype "power_in"))
      (node (ref "U3") (pin "1") (pinfunction "GND_1") (pintype "power_in"))
    )
    (net (code "45") (name "GND") (class "Default") (node (ref "JP1") (pin "2") (pintype "passive")))
    (net (code "46") (name "Net-(D2-A)") (class "Default")
      (node (ref "D2") (pin "1") (pinfunction "A_1") (pintype "passive"))
      (node (ref "R46") (pin "1") (pinfunction "1_1") (pintype "passive"))
    )
    (net (code "47") (name "Net-(D3-A)") (class "Default")
      (node (ref "D3") (pin "1") (pinfunction "A_1") (pintype "passive"))
      (node (ref "R47") (pin "1") (pinfunction "1_1") (pintype "passive"))
    )
    (net (code "48") (name "Net-(D4-A)") (class "Default")
      (node (ref "D4") (pin "1") (pinfunction "A_1") (pintype "passive"))
      (node (ref "R48") (pin "1") (pinfunction "1_1") (pintype "passive"))
    )
    (net (code "49") (name "Net-(D5-A)") (class "Default")
      (node (ref "D5") (pin "1") (pinfunction "A_1") (pintype "passive"))
      (node (ref "R49") (pin "1") (pinfunction "1_1") (pintype "passive"))
    )
    (net (code "50") (name "Net-(D6-A)") (class "Default")
      (node (ref "D6") (pin "1") (pinfunction "A_1") (pintype "passive"))
      (node (ref "R50") (pin "1") (pinfunction "1_1") (pintype "passive"))
    )
    (net (code "51") (name "Net-(J4-Pad2)") (class "Default")
      (node (ref "J4") (pin "2") (pinfunction "2_2") (pintype "passive"))
      (node (ref "J5") (pin "1") (pinfunction "1_1") (pintype "passive"))
    )
    (net (code "52") (name "Net-(J5-Pad2)") (class "Default")
      (node (ref "J5") (pin "2") (pinfunction "2_2") (pintype "passive"))
      (node (ref "J6") (pin "1") (pinfunction "1_1") (pintype "passive"))
    )
    (net (code "53") (name "Net-(Q1-B)") (class "Default")
      (node (ref "Q1") (pin "1") (pinfunction "B_1") (pintype "passive"))
      (node (ref "R14") (pin "1") (pinfunction "1_1") (pintype "passive"))
    )
    (net (code "54") (name "Net-(Q1-C)") (class "Default")
      (node (ref "Q1") (pin "3") (pinfunction "C_3") (pintype "passive"))
      (node (ref "SP1") (pin "2") (pinfunction "-_2") (pintype "passive"))
    )
    (net (code "55") (name "Net-(R11-Pad2)") (class "Default")
      (node (ref "R11") (pin "2") (pinfunction "2_2") (pintype "passive"))
      (node (ref "R9") (pin "2") (pinfunction "2_2") (pintype "passive"))
      (node (ref "S1") (pin "1") (pinfunction "1_1") (pintype "passive"))
    )
    (net (code "56") (name "Net-(U2-RS)") (class "Default")
      (node (ref "R13") (pin "2") (pinfunction "2_2") (pintype "passive"))
      (node (ref "U2") (pin "8") (pinfunction "RS_8") (pintype "input"))
    )
    (net (code "57") (name "unconnected-(J2-Pad5)") (class "Default")
      (node (ref "J2") (pin "5") (pinfunction "5_5") (pintype "passive+no_connect"))
    )
    (net (code "58") (name "unconnected-(J6-Pad2)") (class "Default")
      (node (ref "J6") (pin "2") (pinfunction "2_2") (pintype "passive"))
    )
    (net (code "59") (name "unconnected-(U2-VREF-Pad5)") (class "Default")
      (node (ref "U2") (pin "5") (pinfunction "VREF_5") (pintype "passive"))
    )
  )
)
